# LT5560.net
KiCad netlist of a schematic drawn in Altium Designer
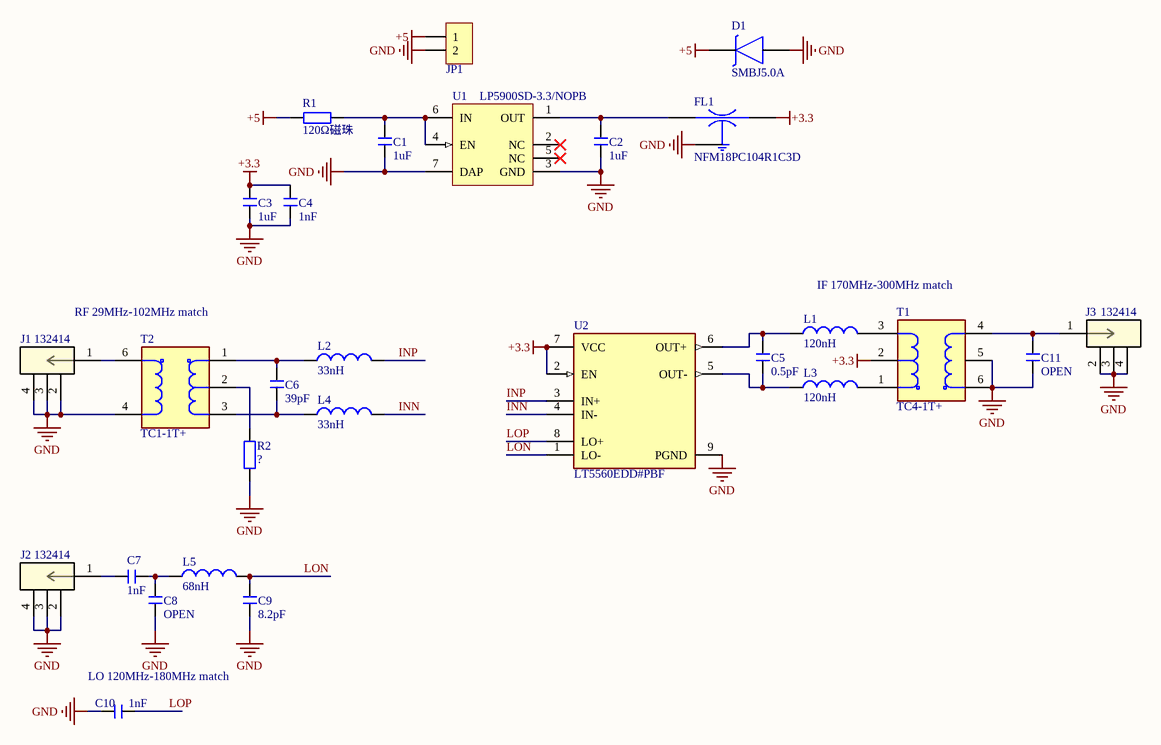
[diagram p0: LT5560.SchDoc]

(export (version "E")
  (design (tool "Eeschema 10.0.6"))
  (components
    (comp (ref "C1")
      (value "1uF")
      (footprint "C 0603_L")
      (description "贴片电容")
      (libsource (lib "01 - 电容-电阻-电感") (part "C"))
    )
    (comp (ref "C2")
      (value "1uF")
      (footprint "C 0603_L")
      (description "贴片电容")
      (libsource (lib "01 - 电容-电阻-电感") (part "C"))
    )
    (comp (ref "C3")
      (value "1uF")
      (footprint "C 0603_L")
      (description "贴片电容")
      (libsource (lib "01 - 电容-电阻-电感") (part "C"))
    )
    (comp (ref "C4")
      (value "1nF")
      (footprint "C 0603_L")
      (description "贴片电容")
      (libsource (lib "01 - 电容-电阻-电感") (part "C"))
    )
    (comp (ref "C5")
      (value "0.5pF")
      (footprint "C 0603_L")
      (description "贴片电容")
      (libsource (lib "01 - 电容-电阻-电感") (part "C"))
    )
    (comp (ref "C6")
      (value "39pF")
      (footprint "C 0603_L")
      (description "贴片电容")
      (libsource (lib "01 - 电容-电阻-电感") (part "C"))
    )
    (comp (ref "C7")
      (value "1nF")
      (footprint "C 0603_L")
      (description "贴片电容")
      (libsource (lib "01 - 电容-电阻-电感") (part "C"))
    )
    (comp (ref "C8")
      (value "OPEN")
      (footprint "C 0603_L")
      (description "贴片电容")
      (libsource (lib "01 - 电容-电阻-电感") (part "C"))
    )
    (comp (ref "C9")
      (value "8.2pF")
      (footprint "C 0603_L")
      (description "贴片电容")
      (libsource (lib "01 - 电容-电阻-电感") (part "C"))
    )
    (comp (ref "C10")
      (value "1nF")
      (footprint "C 0603_L")
      (description "贴片电容")
      (libsource (lib "01 - 电容-电阻-电感") (part "C"))
    )
    (comp (ref "C11")
      (value "OPEN")
      (footprint "C 0603_L")
      (description "贴片电容")
      (libsource (lib "01 - 电容-电阻-电感") (part "C"))
    )
    (comp (ref "D1")
      (value "SMBJ5.0A")
      (footprint "SMBJX.XA_Series_TVS:SMBJ5.0A")
      (description "SMBJX.XA Seires TVS")
      (fields (field (name "MF") "Littelfuse"))
      (libsource (lib "SMBJX.XA_Series_TVS") (part "SMBJ5.0A"))
    )
    (comp (ref "FL1")
      (value "NFM18PC104R1C3D")
      (footprint "FIL_NFM18PC104R1C3D")
      (description "SMD Capacitor with Capacitance: 0.10uF Tol. 20%. Rated Voltage: 16Vdc")
      (fields (field (name "MF") "Murata") (field (name "DIGI-KEY_PART_NUMBER") "490-6969-1-ND"))
      (libsource (lib "NFM18PC104R1C3D") (part "NFM18PC104R1C3D"))
    )
    (comp (ref "J1")
      (value "132414")
      (footprint "CONN_132414_AMP")
      (description "No Description Available")
      (fields (field (name "COPYRIGHT") "Copyright (C) 2022 Ultra Librarian. All rights reserved."))
      (libsource (lib "细针大偏脚SMA(用这个)") (part "132414"))
    )
    (comp (ref "J2")
      (value "132414")
      (footprint "CONN_132414_AMP")
      (description "No Description Available")
      (fields (field (name "COPYRIGHT") "Copyright (C) 2022 Ultra Librarian. All rights reserved."))
      (libsource (lib "细针大偏脚SMA(用这个)") (part "132414"))
    )
    (comp (ref "J3")
      (value "132414")
      (footprint "CONN_132414_AMP")
      (description "No Description Available")
      (fields (field (name "COPYRIGHT") "Copyright (C) 2022 Ultra Librarian. All rights reserved."))
      (libsource (lib "") (part "132414_1"))
    )
    (comp (ref "JP1")
      (value "HDR-1X2")
      (footprint "KF2510-LI-2P")
      (description "2P接插件")
      (libsource (lib "18 - 接插件-脚距2.54mm (100mil) ") (part "Header 2"))
    )
    (comp (ref "L1")
      (value "120nH")
      (footprint "L 0603")
      (description "小功率贴片电感")
      (libsource (lib "01 - 电容-电阻-电感") (part "L"))
    )
    (comp (ref "L2")
      (value "33nH")
      (footprint "L 0603")
      (description "小功率贴片电感")
      (libsource (lib "01 - 电容-电阻-电感") (part "L"))
    )
    (comp (ref "L3")
      (value "120nH")
      (footprint "L 0603")
      (description "小功率贴片电感")
      (libsource (lib "01 - 电容-电阻-电感") (part "L"))
    )
    (comp (ref "L4")
      (value "33nH")
      (footprint "L 0603")
      (description "小功率贴片电感")
      (libsource (lib "01 - 电容-电阻-电感") (part "L"))
    )
    (comp (ref "L5")
      (value "68nH")
      (footprint "L 0603")
      (description "小功率贴片电感")
      (libsource (lib "01 - 电容-电阻-电感") (part "L"))
    )
    (comp (ref "R1")
      (value "120Ω磁珠")
      (footprint "R 0603_L")
      (description "贴片电阻")
      (libsource (lib "01 - 电容-电阻-电感") (part "R"))
    )
    (comp (ref "R2")
      (value "?")
      (footprint "R 0603_L")
      (description "贴片电阻")
      (libsource (lib "01 - 电容-电阻-电感") (part "R"))
    )
    (comp (ref "T1")
      (value "TC4-1T+")
      (footprint "TC4-1T+-Footprint-1")
      (description "Xfmr, Isolation, 50 ohm, 4: 1, 0.5-300 MHz, SMT")
      (libsource (lib "TC4-1T+") (part "TC4-1T+"))
    )
    (comp (ref "T2")
      (value "TC1-1T+")
      (footprint "FP-TC1-1-13M+-MFG")
      (description "RF Transformer 1: 1 5 Terminal SMD")
      (libsource (lib "TC1-1T+") (part "CMP-00025-00004-7"))
    )
    (comp (ref "U1")
      (value "LP5900SD-3.3/NOPB")
      (footprint "LP5900-3.3/NOPB")
      (fields (field (name "MANUFACTURER") "Texas Instruments"))
      (libsource (lib "LP5900-3.3") (part "LP5900SD-3.3/NOPB"))
    )
    (comp (ref "U2")
      (value "LT5560EDD#PBF")
      (footprint "FP-DD-8-05-08-1698-MFG")
      (description "IC MIXER 10KHZ-4GHZ UP/DWN 8DFN")
      (libsource (lib "LT5560EDD") (part "LT5560EDD"))
    )
  )
  (nets
    (net (code "1") (name "+3.3") (class "Default")
      (node (ref "C3") (pin "2") (pinfunction "2_2") (pintype "passive"))
      (node (ref "C4") (pin "2") (pinfunction "2_2") (pintype "passive"))
      (node (ref "FL1") (pin "3") (pinfunction "OUT_3") (pintype "passive"))
      (node (ref "T1") (pin "2") (pinfunction "SECONDARY_2") (pintype "passive"))
      (node (ref "U2") (pin "2") (pinfunction "EN_2") (pintype "input"))
      (node (ref "U2") (pin "7") (pinfunction "VCC_7") (pintype "power_in"))
    )
    (net (code "2") (name "+5") (class "Default")
      (node (ref "D1") (pin "1") (pinfunction "K_1") (pintype "passive"))
      (node (ref "JP1") (pin "1") (pinfunction "1_1") (pintype "passive"))
      (node (ref "R1") (pin "1") (pinfunction "1_1") (pintype "passive"))
    )
    (net (code "3") (name "/INN") (class "Default")
      (node (ref "L4") (pin "2") (pinfunction "2_2") (pintype "passive"))
      (node (ref "U2") (pin "4") (pinfunction "IN-_4") (pintype "tri_state"))
    )
    (net (code "4") (name "/INP") (class "Default")
      (node (ref "L2") (pin "2") (pinfunction "2_2") (pintype "passive"))
      (node (ref "U2") (pin "3") (pinfunction "IN+_3") (pintype "tri_state"))
    )
    (net (code "5") (name "/LON") (class "Default")
      (node (ref "C9") (pin "2") (pinfunction "2_2") (pintype "passive"))
      (node (ref "L5") (pin "2") (pinfunction "2_2") (pintype "passive"))
      (node (ref "U2") (pin "1") (pinfunction "LO-_1") (pintype "passive"))
    )
    (net (code "6") (name "/LOP") (class "Default")
      (node (ref "C10") (pin "2") (pinfunction "2_2") (pintype "passive"))
      (node (ref "U2") (pin "8") (pinfunction "LO+_8") (pintype "passive"))
    )
    (net (code "7") (name "GND") (class "Default")
      (node (ref "C1") (pin "1") (pinfunction "1_1") (pintype "passive"))
      (node (ref "C10") (pin "1") (pinfunction "1_1") (pintype "passive"))
      (node (ref "C11") (pin "1") (pinfunction "1_1") (pintype "passive"))
      (node (ref "C2") (pin "1") (pinfunction "1_1") (pintype "passive"))
      (node (ref "C3") (pin "1") (pinfunction "1_1") (pintype "passive"))
      (node (ref "C4") (pin "1") (pinfunction "1_1") (pintype "passive"))
      (node (ref "C8") (pin "1") (pinfunction "1_1") (pintype "passive"))
      (node (ref "C9") (pin "1") (pinfunction "1_1") (pintype "passive"))
      (node (ref "D1") (pin "2") (pinfunction "A_2") (pintype "passive"))
      (node (ref "FL1") (pin "2") (pinfunction "GND_2") (pintype "power_in"))
      (node (ref "J1") (pin "2") (pinfunction "2_2") (pintype "passive"))
      (node (ref "J1") (pin "3") (pinfunction "3_3") (pintype "passive"))
      (node (ref "J1") (pin "4") (pinfunction "4_4") (pintype "passive"))
      (node (ref "J2") (pin "2") (pinfunction "2_2") (pintype "passive"))
      (node (ref "J2") (pin "3") (pinfunction "3_3") (pintype "passive"))
      (node (ref "J2") (pin "4") (pinfunction "4_4") (pintype "passive"))
      (node (ref "J3") (pin "2") (pinfunction "2_2") (pintype "passive"))
      (node (ref "J3") (pin "3") (pinfunction "3_3") (pintype "passive"))
      (node (ref "J3") (pin "4") (pinfunction "4_4") (pintype "passive"))
      (node (ref "JP1") (pin "2") (pinfunction "2_2") (pintype "passive"))
      (node (ref "R2") (pin "1") (pinfunction "1_1") (pintype "passive"))
      (node (ref "T1") (pin "5") (pinfunction "NC_5") (pintype "passive"))
      (node (ref "T1") (pin "6") (pinfunction "PRIMARY_DOT_6") (pintype "passive"))
      (node (ref "T2") (pin "4") (pinfunction "PRIMARY_4") (pintype "passive"))
      (node (ref "U1") (pin "3") (pinfunction "GND_3") (pintype "power_in"))
      (node (ref "U1") (pin "7") (pinfunction "DAP_7") (pintype "power_in"))
      (node (ref "U2") (pin "9") (pinfunction "PGND_9") (pintype "power_in"))
    )
    (net (code "8") (name "Net-(C7-Pad1)") (class "Default")
      (node (ref "C7") (pin "1") (pinfunction "1_1") (pintype "passive"))
      (node (ref "J2") (pin "1") (pinfunction "1_1") (pintype "passive"))
    )
    (net (code "9") (name "Net-(C7-Pad2)") (class "Default")
      (node (ref "C7") (pin "2") (pinfunction "2_2") (pintype "passive"))
      (node (ref "C8") (pin "2") (pinfunction "2_2") (pintype "passive"))
      (node (ref "L5") (pin "1") (pinfunction "1_1") (pintype "passive"))
    )
    (net (code "10") (name "Net-(FL1-IN)") (class "Default")
      (node (ref "C2") (pin "2") (pinfunction "2_2") (pintype "passive"))
      (node (ref "FL1") (pin "1") (pinfunction "IN_1") (pintype "passive"))
      (node (ref "U1") (pin "1") (pinfunction "OUT_1") (pintype "power_in"))
    )
    (net (code "11") (name "Net-(T1-PRIMARY)") (class "Default")
      (node (ref "C11") (pin "2") (pinfunction "2_2") (pintype "passive"))
      (node (ref "J3") (pin "1") (pinfunction "1_1") (pintype "passive"))
      (node (ref "T1") (pin "4") (pinfunction "PRIMARY_4") (pintype "passive"))
    )
    (net (code "12") (name "Net-(T1-SECONDARY_DOT)") (class "Default")
      (node (ref "L3") (pin "2") (pinfunction "2_2") (pintype "passive"))
      (node (ref "T1") (pin "1") (pinfunction "SECONDARY_DOT_1") (pintype "passive"))
    )
    (net (code "13") (name "Net-(T1-SECONDARY_MID)") (class "Default")
      (node (ref "L1") (pin "2") (pinfunction "2_2") (pintype "passive"))
      (node (ref "T1") (pin "3") (pinfunction "SECONDARY_MID_3") (pintype "passive"))
    )
    (net (code "14") (name "Net-(T2-PRIMARY_DOT)") (class "Default")
      (node (ref "J1") (pin "1") (pinfunction "1_1") (pintype "passive"))
      (node (ref "T2") (pin "6") (pinfunction "PRIMARY_DOT_6") (pintype "passive"))
    )
    (net (code "15") (name "Net-(T2-SECONDARY)") (class "Default")
      (node (ref "R2") (pin "2") (pinfunction "2_2") (pintype "passive"))
      (node (ref "T2") (pin "2") (pinfunction "SECONDARY_2") (pintype "passive"))
    )
    (net (code "16") (name "Net-(T2-SECONDARY_DOT)") (class "Default")
      (node (ref "C6") (pin "2") (pinfunction "2_2") (pintype "passive"))
      (node (ref "L2") (pin "1") (pinfunction "1_1") (pintype "passive"))
      (node (ref "T2") (pin "1") (pinfunction "SECONDARY_DOT_1") (pintype "passive"))
    )
    (net (code "17") (name "Net-(T2-SECONDARY_MID)") (class "Default")
      (node (ref "C6") (pin "1") (pinfunction "1_1") (pintype "passive"))
      (node (ref "L4") (pin "1") (pinfunction "1_1") (pintype "passive"))
      (node (ref "T2") (pin "3") (pinfunction "SECONDARY_MID_3") (pintype "passive"))
    )
    (net (code "18") (name "Net-(U1-EN)") (class "Default")
      (node (ref "C1") (pin "2") (pinfunction "2_2") (pintype "passive"))
      (node (ref "R1") (pin "2") (pinfunction "2_2") (pintype "passive"))
      (node (ref "U1") (pin "4") (pinfunction "EN_4") (pintype "input"))
      (node (ref "U1") (pin "6") (pinfunction "IN_6") (pintype "power_in"))
    )
    (net (code "19") (name "Net-(U2-OUT+)") (class "Default")
      (node (ref "C5") (pin "2") (pinfunction "2_2") (pintype "passive"))
      (node (ref "L1") (pin "1") (pinfunction "1_1") (pintype "passive"))
      (node (ref "U2") (pin "6") (pinfunction "OUT+_6") (pintype "output"))
    )
    (net (code "20") (name "Net-(U2-OUT-)") (class "Default")
      (node (ref "C5") (pin "1") (pinfunction "1_1") (pintype "passive"))
      (node (ref "L3") (pin "1") (pinfunction "1_1") (pintype "passive"))
      (node (ref "U2") (pin "5") (pinfunction "OUT-_5") (pintype "output"))
    )
    (net (code "21") (name "unconnected-(U1-NC-Pad2)") (class "Default")
      (node (ref "U1") (pin "2") (pinfunction "NC_2") (pintype "passive+no_connect"))
    )
    (net (code "22") (name "unconnected-(U1-NC-Pad5)") (class "Default")
      (node (ref "U1") (pin "5") (pinfunction "NC_5") (pintype "passive+no_connect"))
    )
  )
)
